# stlink.net
KiCad netlist of a schematic drawn in Altium Designer
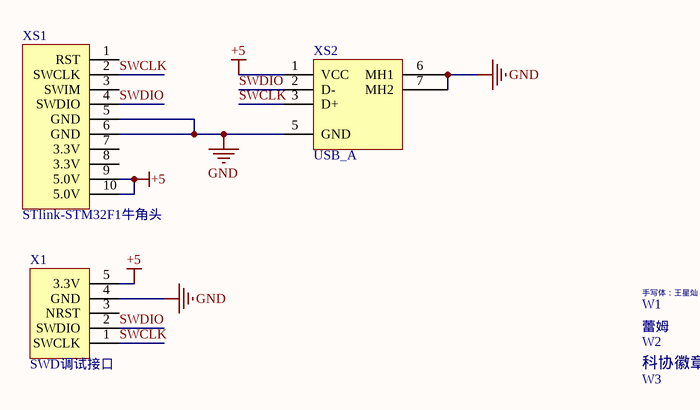
[diagram p0: stlink烧录转接板.SchDoc]

(export (version "E")
  (design (tool "Eeschema 10.0.6"))
  (components
    (comp (ref "W1") (value "手写体：王星灿") (footprint "手写体：王星灿") (libsource (lib "丝印库") (part "手写体：王星灿")))
    (comp (ref "W2") (value "蕾姆") (footprint "蕾姆360-340mil") (libsource (lib "丝印库") (part "蕾姆")))
    (comp (ref "W3") (value "科协徽章") (footprint "科协徽章2（310-310）") (libsource (lib "丝印库") (part "科协徽章")))
    (comp (ref "X1") (value "SWD调试接口") (footprint "SWD调试接口") (libsource (lib "第一次绘制库") (part "SWD调试接口")))
    (comp (ref "XS1")
      (value "STlink-STM32F1牛角头")
      (footprint "STlink-STM32F1牛角头")
      (libsource (lib "第一次绘制库") (part "STlink-STM32F1牛角头"))
    )
    (comp (ref "XS2") (value "USB_A") (footprint "USB_A母口180度贴片") (libsource (lib "接插件库") (part "USB_A母座")))
  )
  (nets
    (net (code "1") (name "+5") (class "Default")
      (node (ref "X1") (pin "5") (pinfunction "3.3V_5") (pintype "passive"))
      (node (ref "XS1") (pin "10") (pinfunction "5.0V_10") (pintype "passive"))
      (node (ref "XS1") (pin "9") (pinfunction "5.0V_9") (pintype "passive"))
      (node (ref "XS2") (pin "1") (pinfunction "VCC_1") (pintype "passive"))
    )
    (net (code "2") (name "/SWCLK") (class "Default")
      (node (ref "X1") (pin "1") (pinfunction "SWCLK_1") (pintype "passive"))
      (node (ref "XS1") (pin "2") (pinfunction "SWCLK_2") (pintype "passive"))
      (node (ref "XS2") (pin "3") (pinfunction "D+_3") (pintype "passive"))
    )
    (net (code "3") (name "/SWDIO") (class "Default")
      (node (ref "X1") (pin "2") (pinfunction "SWDIO_2") (pintype "passive"))
      (node (ref "XS1") (pin "4") (pinfunction "SWDIO_4") (pintype "passive"))
      (node (ref "XS2") (pin "2") (pinfunction "D-_2") (pintype "passive"))
    )
    (net (code "4") (name "GND") (class "Default")
      (node (ref "X1") (pin "4") (pinfunction "GND_4") (pintype "passive"))
      (node (ref "XS1") (pin "5") (pinfunction "GND_5") (pintype "passive"))
      (node (ref "XS1") (pin "6") (pinfunction "GND_6") (pintype "passive"))
      (node (ref "XS2") (pin "5") (pinfunction "GND_5") (pintype "passive"))
      (node (ref "XS2") (pin "6") (pinfunction "MH1_6") (pintype "passive"))
      (node (ref "XS2") (pin "7") (pinfunction "MH2_7") (pintype "passive"))
    )
    (net (code "5") (name "unconnected-(X1-NRST-Pad3)") (class "Default")
      (node (ref "X1") (pin "3") (pinfunction "NRST_3") (pintype "passive"))
    )
    (net (code "6") (name "unconnected-(XS1-3.3V-Pad7)") (class "Default")
      (node (ref "XS1") (pin "7") (pinfunction "3.3V_7") (pintype "passive"))
    )
    (net (code "7") (name "unconnected-(XS1-3.3V-Pad8)") (class "Default")
      (node (ref "XS1") (pin "8") (pinfunction "3.3V_8") (pintype "passive"))
    )
    (net (code "8") (name "unconnected-(XS1-RST-Pad1)") (class "Default")
      (node (ref "XS1") (pin "1") (pinfunction "RST_1") (pintype "passive"))
    )
    (net (code "9") (name "unconnected-(XS1-SWIM-Pad3)") (class "Default")
      (node (ref "XS1") (pin "3") (pinfunction "SWIM_3") (pintype "passive"))
    )
  )
)
